# wrist_band.net
KiCad netlist of a schematic drawn in Altium Designer
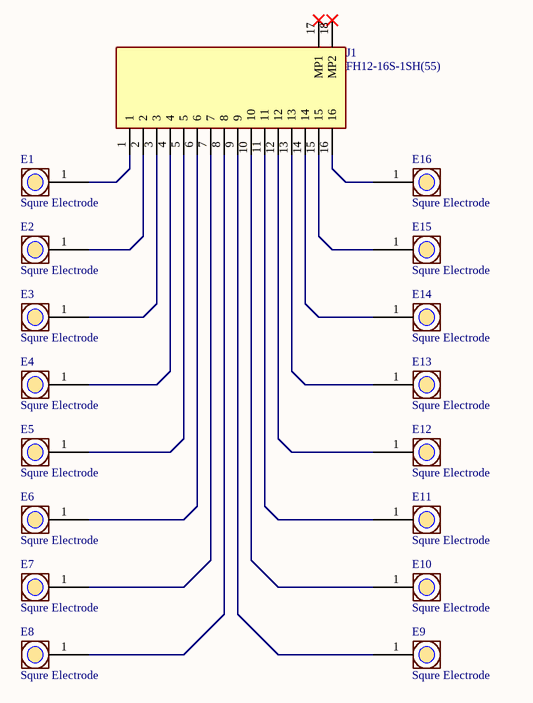
[diagram p0: wrist_band.SchDoc]

(export (version "E")
  (design (tool "Eeschema 10.0.6"))
  (components
    (comp (ref "E1") (value "Squre Electrode") (footprint "E") (libsource (lib "electrode_sq") (part "E")))
    (comp (ref "E2") (value "Squre Electrode") (footprint "E") (libsource (lib "electrode_sq") (part "E")))
    (comp (ref "E3") (value "Squre Electrode") (footprint "E") (libsource (lib "electrode_sq") (part "E")))
    (comp (ref "E4") (value "Squre Electrode") (footprint "E") (libsource (lib "electrode_sq") (part "E")))
    (comp (ref "E5") (value "Squre Electrode") (footprint "E") (libsource (lib "electrode_sq") (part "E")))
    (comp (ref "E6") (value "Squre Electrode") (footprint "E") (libsource (lib "electrode_sq") (part "E")))
    (comp (ref "E7") (value "Squre Electrode") (footprint "E") (libsource (lib "electrode_sq") (part "E")))
    (comp (ref "E8") (value "Squre Electrode") (footprint "E") (libsource (lib "electrode_sq") (part "E")))
    (comp (ref "E9") (value "Squre Electrode") (footprint "E") (libsource (lib "electrode_sq") (part "E")))
    (comp (ref "E10") (value "Squre Electrode") (footprint "E") (libsource (lib "electrode_sq") (part "E")))
    (comp (ref "E11") (value "Squre Electrode") (footprint "E") (libsource (lib "electrode_sq") (part "E")))
    (comp (ref "E12") (value "Squre Electrode") (footprint "E") (libsource (lib "electrode_sq") (part "E")))
    (comp (ref "E13") (value "Squre Electrode") (footprint "E") (libsource (lib "electrode_sq") (part "E")))
    (comp (ref "E14") (value "Squre Electrode") (footprint "E") (libsource (lib "electrode_sq") (part "E")))
    (comp (ref "E15") (value "Squre Electrode") (footprint "E") (libsource (lib "electrode_sq") (part "E")))
    (comp (ref "E16") (value "Squre Electrode") (footprint "E") (libsource (lib "electrode_sq") (part "E")))
    (comp (ref "J1")
      (value "FH12-16S-1SH(55)")
      (footprint "FH12-16S-1SH(55)")
      (libsource (lib "FH12-16S-1SH(55)") (part "FH12-16S-1SH(55)"))
    )
  )
  (nets
    (net (code "1") (name "Net-(E1-Pad1)") (class "Default")
      (node (ref "E1") (pin "1") (pinfunction "1_1") (pintype "passive"))
      (node (ref "J1") (pin "1") (pinfunction "1_1") (pintype "passive"))
    )
    (net (code "2") (name "Net-(E2-Pad1)") (class "Default")
      (node (ref "E2") (pin "1") (pinfunction "1_1") (pintype "passive"))
      (node (ref "J1") (pin "2") (pinfunction "2_2") (pintype "passive"))
    )
    (net (code "3") (name "Net-(E3-Pad1)") (class "Default")
      (node (ref "E3") (pin "1") (pinfunction "1_1") (pintype "passive"))
      (node (ref "J1") (pin "3") (pinfunction "3_3") (pintype "passive"))
    )
    (net (code "4") (name "Net-(E4-Pad1)") (class "Default")
      (node (ref "E4") (pin "1") (pinfunction "1_1") (pintype "passive"))
      (node (ref "J1") (pin "4") (pinfunction "4_4") (pintype "passive"))
    )
    (net (code "5") (name "Net-(E5-Pad1)") (class "Default")
      (node (ref "E5") (pin "1") (pinfunction "1_1") (pintype "passive"))
      (node (ref "J1") (pin "5") (pinfunction "5_5") (pintype "passive"))
    )
    (net (code "6") (name "Net-(E6-Pad1)") (class "Default")
      (node (ref "E6") (pin "1") (pinfunction "1_1") (pintype "passive"))
      (node (ref "J1") (pin "6") (pinfunction "6_6") (pintype "passive"))
    )
    (net (code "7") (name "Net-(E7-Pad1)") (class "Default")
      (node (ref "E7") (pin "1") (pinfunction "1_1") (pintype "passive"))
      (node (ref "J1") (pin "7") (pinfunction "7_7") (pintype "passive"))
    )
    (net (code "8") (name "Net-(E8-Pad1)") (class "Default")
      (node (ref "E8") (pin "1") (pinfunction "1_1") (pintype "passive"))
      (node (ref "J1") (pin "8") (pinfunction "8_8") (pintype "passive"))
    )
    (net (code "9") (name "Net-(E9-Pad1)") (class "Default")
      (node (ref "E9") (pin "1") (pinfunction "1_1") (pintype "passive"))
      (node (ref "J1") (pin "9") (pinfunction "9_9") (pintype "passive"))
    )
    (net (code "10") (name "Net-(E10-Pad1)") (class "Default")
      (node (ref "E10") (pin "1") (pinfunction "1_1") (pintype "passive"))
      (node (ref "J1") (pin "10") (pinfunction "10_10") (pintype "passive"))
    )
    (net (code "11") (name "Net-(E11-Pad1)") (class "Default")
      (node (ref "E11") (pin "1") (pinfunction "1_1") (pintype "passive"))
      (node (ref "J1") (pin "11") (pinfunction "11_11") (pintype "passive"))
    )
    (net (code "12") (name "Net-(E12-Pad1)") (class "Default")
      (node (ref "E12") (pin "1") (pinfunction "1_1") (pintype "passive"))
      (node (ref "J1") (pin "12") (pinfunction "12_12") (pintype "passive"))
    )
    (net (code "13") (name "Net-(E13-Pad1)") (class "Default")
      (node (ref "E13") (pin "1") (pinfunction "1_1") (pintype "passive"))
      (node (ref "J1") (pin "13") (pinfunction "13_13") (pintype "passive"))
    )
    (net (code "14") (name "Net-(E14-Pad1)") (class "Default")
      (node (ref "E14") (pin "1") (pinfunction "1_1") (pintype "passive"))
      (node (ref "J1") (pin "14") (pinfunction "14_14") (pintype "passive"))
    )
    (net (code "15") (name "Net-(E15-Pad1)") (class "Default")
      (node (ref "E15") (pin "1") (pinfunction "1_1") (pintype "passive"))
      (node (ref "J1") (pin "15") (pinfunction "15_15") (pintype "passive"))
    )
    (net (code "16") (name "Net-(E16-Pad1)") (class "Default")
      (node (ref "E16") (pin "1") (pinfunction "1_1") (pintype "passive"))
      (node (ref "J1") (pin "16") (pinfunction "16_16") (pintype "passive"))
    )
    (net (code "17") (name "unconnected-(J1-MP1-Pad17)") (class "Default")
      (node (ref "J1") (pin "17") (pinfunction "MP1_17") (pintype "passive+no_connect"))
    )
    (net (code "18") (name "unconnected-(J1-MP2-Pad18)") (class "Default")
      (node (ref "J1") (pin "18") (pinfunction "MP2_18") (pintype "passive+no_connect"))
    )
  )
)
